# Placa_Alimentaci_n.net
KiCad netlist of a schematic drawn in Altium Designer
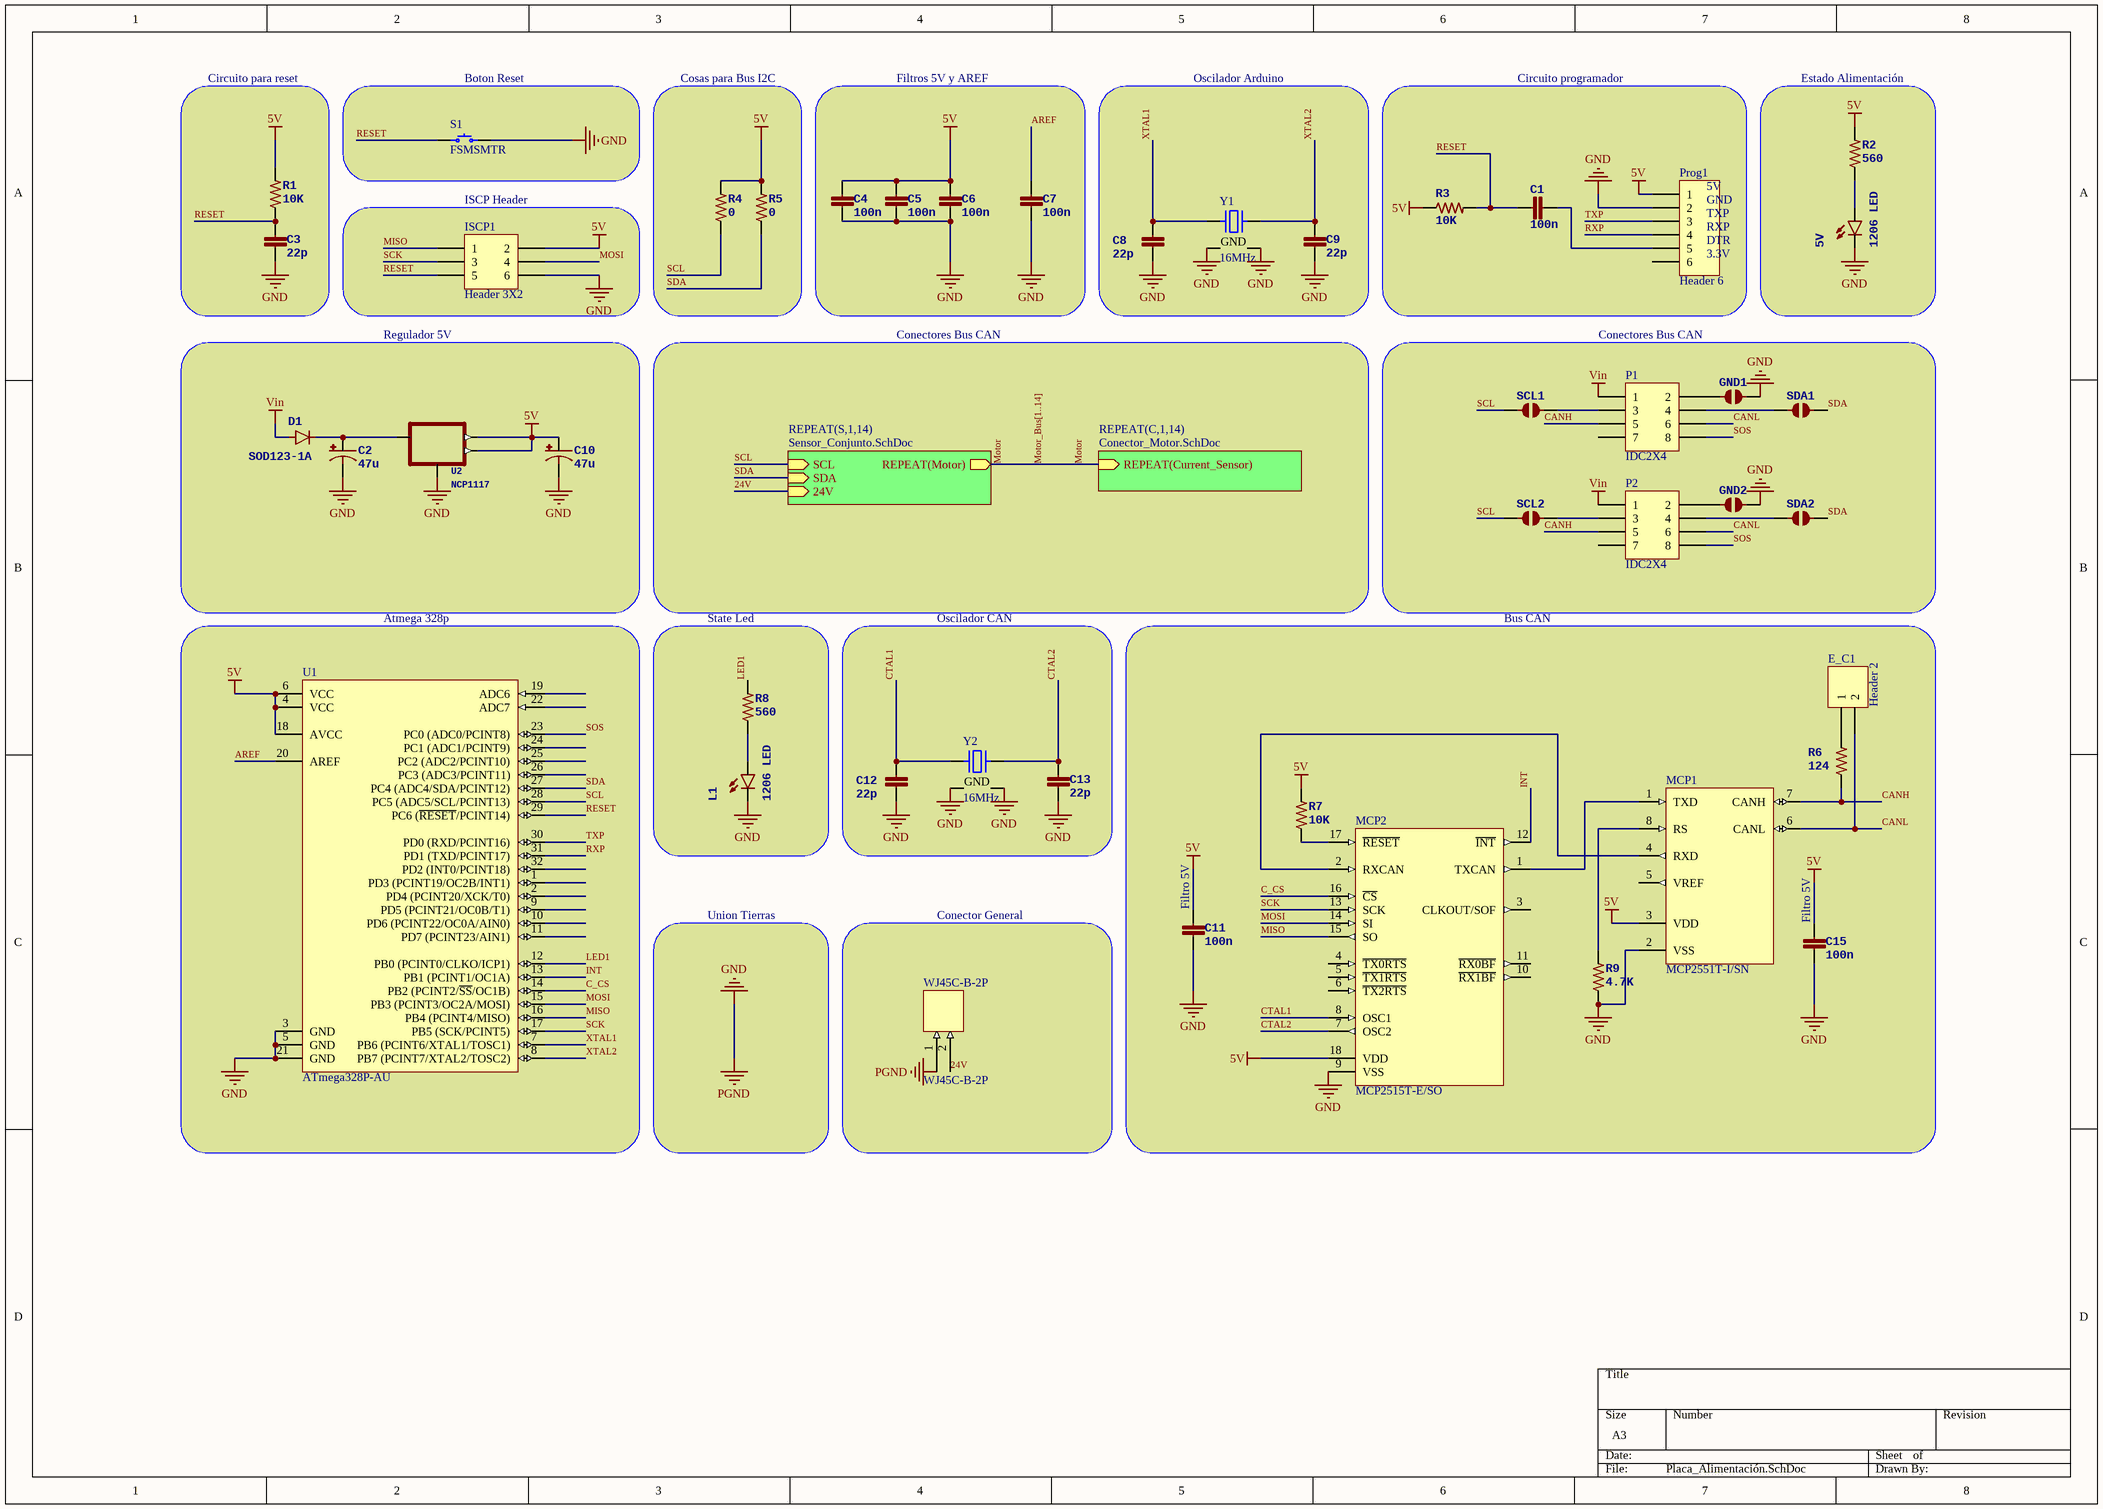
[diagram p0: Placa_Alimentación.SchDoc]

(export (version "E")
  (design (tool "Eeschema 10.0.6"))
  (components
    (comp (ref "5V")
      (value "1206 LED")
      (footprint "SparkFun-LED:LED-1206")
      (libsource (lib "SparkFun-LED") (part "LED1206"))
    )
    (comp (ref "C1")
      (value "100n")
      (footprint "SparkFun-Passives:0805")
      (libsource (lib "") (part "CAP0805_1"))
    )
    (comp (ref "C2")
      (value "47u")
      (footprint "PANASONIC_D")
      (libsource (lib "SparkFun-Capacitors") (part "47UF-50V-20%(ELECT)"))
    )
    (comp (ref "C3")
      (value "22p")
      (footprint "SparkFun-Passives:0805")
      (libsource (lib "SparkFun-Passives") (part "CAP0805"))
    )
    (comp (ref "C4")
      (value "100n")
      (footprint "SparkFun-Passives:0805")
      (libsource (lib "SparkFun-Passives") (part "CAP0805"))
    )
    (comp (ref "C5")
      (value "100n")
      (footprint "SparkFun-Passives:0805")
      (libsource (lib "SparkFun-Passives") (part "CAP0805"))
    )
    (comp (ref "C6")
      (value "100n")
      (footprint "SparkFun-Passives:0805")
      (libsource (lib "SparkFun-Passives") (part "CAP0805"))
    )
    (comp (ref "C7")
      (value "100n")
      (footprint "SparkFun-Passives:0805")
      (libsource (lib "SparkFun-Passives") (part "CAP0805"))
    )
    (comp (ref "C8")
      (value "22p")
      (footprint "SparkFun-Passives:0805")
      (libsource (lib "SparkFun-Passives") (part "CAP0805"))
    )
    (comp (ref "C9")
      (value "22p")
      (footprint "SparkFun-Passives:0805")
      (libsource (lib "SparkFun-Passives") (part "CAP0805"))
    )
    (comp (ref "C10")
      (value "47u")
      (footprint "PANASONIC_D")
      (libsource (lib "SparkFun-Capacitors") (part "47UF-50V-20%(ELECT)"))
    )
    (comp (ref "C11")
      (value "100n")
      (footprint "SparkFun-Passives:0805")
      (libsource (lib "SparkFun-Passives") (part "CAP0805"))
    )
    (comp (ref "C12")
      (value "22p")
      (footprint "SparkFun-Passives:0805")
      (libsource (lib "SparkFun-Passives") (part "CAP0805"))
    )
    (comp (ref "C13")
      (value "22p")
      (footprint "SparkFun-Passives:0805")
      (libsource (lib "SparkFun-Passives") (part "CAP0805"))
    )
    (comp (ref "C15")
      (value "100n")
      (footprint "SparkFun-Passives:0805")
      (libsource (lib "SparkFun-Passives") (part "CAP0805"))
    )
    (comp (ref "D1")
      (value "SOD123-1A")
      (footprint "SOD-123")
      (libsource (lib "SparkFun-DiscreteSemi") (part "DIODESOD123"))
    )
    (comp (ref "E_C1")
      (value "Header 2")
      (footprint "HDR1X2")
      (description "Header, 2-Pin")
      (fields (field (name "PUBLISHER") "Altium Limited"))
      (libsource (lib "Miscellaneous Connectors") (part "Header 2"))
    )
    (comp (ref "GND1")
      (value "JUMPER-PAD-2-NOYES_SILK")
      (footprint "PAD-JUMPER-2-NO_YES_SILK")
      (libsource (lib "SparkFun-Passives") (part "JUMPER-PAD-2-NOYES_SILK"))
    )
    (comp (ref "GND2")
      (value "JUMPER-PAD-2-NOYES_SILK")
      (footprint "PAD-JUMPER-2-NO_YES_SILK")
      (libsource (lib "SparkFun-Passives") (part "JUMPER-PAD-2-NOYES_SILK"))
    )
    (comp (ref "ISCP1")
      (value "Header 3X2")
      (footprint "HDR2X3")
      (description "Header, 3-Pin, Dual row")
      (fields (field (name "PUBLISHER") "Altium Limited"))
      (libsource (lib "Miscellaneous Connectors") (part "Header 3X2"))
    )
    (comp (ref "L1")
      (value "1206 LED")
      (footprint "SparkFun-LED:LED-1206")
      (libsource (lib "SparkFun-LED") (part "LED1206"))
    )
    (comp (ref "MCP1")
      (value "MCP2551T-I/SN")
      (footprint "SOIC-SN8_N")
      (description "High-Speed CAN Transceiver, 8-Pin SOIC, Industrial Temperature, Tape and Reel")
      (fields (field (name "PUBLISHER") "Altium Limited"))
      (libsource (lib "Microchip Interface") (part "MCP2551T-I/SN"))
    )
    (comp (ref "MCP2")
      (value "MCP2515T-E/SO")
      (footprint "SOIC-SO18_N")
      (description "Stand-Alone CAN Controller With SPI Interface, 18-Pin SOIC, Extended Temperature, Tape and Reel")
      (fields (field (name "PUBLISHER") "Altium Limited"))
      (libsource (lib "Microchip Interface") (part "MCP2515T-E/SO"))
    )
    (comp (ref "P1")
      (value "IDC2X4")
      (footprint "IDC2X4")
      (description "Header, 4-Pin, Dual row")
      (fields (field (name "PUBLISHER") "Altium Limited"))
      (libsource (lib "IDC") (part "IDC2X4"))
    )
    (comp (ref "P2")
      (value "IDC2X4")
      (footprint "IDC2X4")
      (description "Header, 4-Pin, Dual row")
      (fields (field (name "PUBLISHER") "Altium Limited"))
      (libsource (lib "IDC") (part "IDC2X4"))
    )
    (comp (ref "Prog1")
      (value "Header 6")
      (footprint "HDR1X6")
      (description "Header, 6-Pin")
      (fields (field (name "PUBLISHER") "Altium Limited"))
      (libsource (lib "Miscellaneous Connectors") (part "Header 6"))
    )
    (comp (ref "R1")
      (value "10K")
      (footprint "SparkFun-Passives:0805")
      (libsource (lib "SparkFun-Passives") (part "RESISTOR0805-RES"))
    )
    (comp (ref "R2")
      (value "560")
      (footprint "SparkFun-Passives:0805")
      (libsource (lib "SparkFun-Passives") (part "RESISTOR0805-RES"))
    )
    (comp (ref "R3")
      (value "10K")
      (footprint "SparkFun-Passives:0805")
      (libsource (lib "SparkFun-Passives") (part "RESISTOR0805-RES"))
    )
    (comp (ref "R4")
      (value "0")
      (footprint "SparkFun-Passives:0805")
      (libsource (lib "SparkFun-Passives") (part "RESISTOR0805-RES"))
    )
    (comp (ref "R5")
      (value "0")
      (footprint "SparkFun-Passives:0805")
      (libsource (lib "SparkFun-Passives") (part "RESISTOR0805-RES"))
    )
    (comp (ref "R6")
      (value "124")
      (footprint "SparkFun-Passives:0805")
      (libsource (lib "SparkFun-Passives") (part "RESISTOR0805-RES"))
    )
    (comp (ref "R7")
      (value "10K")
      (footprint "SparkFun-Passives:0805")
      (libsource (lib "SparkFun-Passives") (part "RESISTOR0805-RES"))
    )
    (comp (ref "R8")
      (value "560")
      (footprint "SparkFun-Passives:0805")
      (libsource (lib "SparkFun-Passives") (part "RESISTOR0805-RES"))
    )
    (comp (ref "R9")
      (value "4.7K")
      (footprint "SparkFun-Passives:0805")
      (libsource (lib "SparkFun-Passives") (part "RESISTOR0805-RES"))
    )
    (comp (ref "S1")
      (value "FSMSMTR")
      (footprint "TE FSMSMTR")
      (description "SWITCH TACTILE SPST-NO 0.05A 24V")
      (fields (field (name "MANUFACTURER") "TE Connectivity Alcoswitch Switches"))
      (libsource (lib "Button - Tactile") (part "SPST-NO 2 PIN"))
    )
    (comp (ref "SCL1")
      (value "JUMPER-PAD-2-NOYES_SILK")
      (footprint "PAD-JUMPER-2-NO_YES_SILK")
      (libsource (lib "SparkFun-Passives") (part "JUMPER-PAD-2-NOYES_SILK"))
    )
    (comp (ref "SCL2")
      (value "JUMPER-PAD-2-NOYES_SILK")
      (footprint "PAD-JUMPER-2-NO_YES_SILK")
      (libsource (lib "SparkFun-Passives") (part "JUMPER-PAD-2-NOYES_SILK"))
    )
    (comp (ref "SDA1")
      (value "JUMPER-PAD-2-NOYES_SILK")
      (footprint "PAD-JUMPER-2-NO_YES_SILK")
      (libsource (lib "SparkFun-Passives") (part "JUMPER-PAD-2-NOYES_SILK"))
    )
    (comp (ref "SDA2")
      (value "JUMPER-PAD-2-NOYES_SILK")
      (footprint "PAD-JUMPER-2-NO_YES_SILK")
      (libsource (lib "SparkFun-Passives") (part "JUMPER-PAD-2-NOYES_SILK"))
    )
    (comp (ref "U1")
      (value "ATmega328P-AU")
      (footprint "32A_N")
      (fields (field (name "PUBLISHER") "Altium Limited"))
      (libsource (lib "Atmel Microcontroller 8-Bit megaAVR") (part "ATmega328P-AU"))
    )
    (comp (ref "U2")
      (value "NCP1117")
      (footprint "SparkFun-IC-Power:SOT223")
      (libsource (lib "SparkFun-IC-Power") (part "V_REG_LM1117SOT223"))
    )
    (comp (ref "WJ45C-B-2P")
      (value "WJ45C-B-2P")
      (footprint "WJ45C-B-2P")
      (libsource (lib "WJ45C") (part "WJ45C-B-2P"))
    )
    (comp (ref "Y1")
      (value "16MHz")
      (footprint "NDK NX3225SA")
      (description "CRYSTAL 16.0000MHZ 8PF SMD")
      (fields (field (name "PART NUMBER") "NX3225SA-16.000MHZ-STD-CSR-1") (field (name "MANUFACTURER") "NDK"))
      (libsource (lib "Oscillator - Crystal") (part "NDK Crystal NX3225SA"))
    )
    (comp (ref "Y2")
      (value "16MHz")
      (footprint "NDK NX3225SA")
      (description "CRYSTAL 16.0000MHZ 8PF SMD")
      (fields (field (name "PART NUMBER") "NX3225SA-16.000MHZ-STD-CSR-1") (field (name "MANUFACTURER") "NDK"))
      (libsource (lib "Oscillator - Crystal") (part "NDK Crystal NX3225SA"))
    )
  )
  (nets
    (net (code "15") (name "/24V") (class "Default") (node (ref "WJ45C-B-2P") (pin "2") (pintype "input")))
    (net (code "16") (name "/AREF") (class "Default")
      (node (ref "C7") (pin "1") (pinfunction "1_1") (pintype "passive"))
      (node (ref "U1") (pin "20") (pinfunction "AREF_20") (pintype "passive"))
    )
    (net (code "17") (name "/CANH") (class "Default")
      (node (ref "MCP1") (pin "7") (pinfunction "CANH_7") (pintype "bidirectional"))
      (node (ref "P1") (pin "5") (pinfunction "5_5") (pintype "passive"))
      (node (ref "P2") (pin "5") (pinfunction "5_5") (pintype "passive"))
      (node (ref "R6") (pin "1") (pinfunction "1_1") (pintype "passive"))
    )
    (net (code "18") (name "/CANL") (class "Default")
      (node (ref "E_C1") (pin "2") (pinfunction "2_2") (pintype "passive"))
      (node (ref "MCP1") (pin "6") (pinfunction "CANL_6") (pintype "bidirectional"))
      (node (ref "P1") (pin "6") (pinfunction "6_6") (pintype "passive"))
      (node (ref "P2") (pin "6") (pinfunction "6_6") (pintype "passive"))
    )
    (net (code "19") (name "/CTAL1") (class "Default")
      (node (ref "C12") (pin "1") (pinfunction "1_1") (pintype "passive"))
      (node (ref "MCP2") (pin "8") (pinfunction "OSC1_8") (pintype "input"))
      (node (ref "Y2") (pin "1") (pinfunction "1_1") (pintype "passive"))
    )
    (net (code "20") (name "/CTAL2") (class "Default")
      (node (ref "C13") (pin "1") (pinfunction "1_1") (pintype "passive"))
      (node (ref "MCP2") (pin "7") (pinfunction "OSC2_7") (pintype "output"))
      (node (ref "Y2") (pin "3") (pinfunction "3_3") (pintype "passive"))
    )
    (net (code "21") (name "/C_CS") (class "Default")
      (node (ref "MCP2") (pin "16") (pinfunction "~{CS}_16") (pintype "input"))
      (node (ref "U1") (pin "14") (pinfunction "PB2_(PCINT2/~{SS}/OC1B)_14") (pintype "bidirectional"))
    )
    (net (code "22") (name "/INT") (class "Default")
      (node (ref "MCP2") (pin "12") (pinfunction "~{INT}_12") (pintype "output"))
      (node (ref "U1") (pin "13") (pinfunction "PB1_(PCINT1/OC1A)_13") (pintype "bidirectional"))
    )
    (net (code "23") (name "/LED1") (class "Default")
      (node (ref "R8") (pin "2") (pinfunction "2_2") (pintype "passive"))
      (node (ref "U1") (pin "12") (pinfunction "PB0_(PCINT0/CLKO/ICP1)_12") (pintype "bidirectional"))
    )
    (net (code "24") (name "/MISO") (class "Default")
      (node (ref "ISCP1") (pin "1") (pinfunction "1_1") (pintype "passive"))
      (node (ref "MCP2") (pin "15") (pinfunction "SO_15") (pintype "output"))
      (node (ref "U1") (pin "16") (pinfunction "PB4_(PCINT4/MISO)_16") (pintype "bidirectional"))
    )
    (net (code "25") (name "/MOSI") (class "Default")
      (node (ref "ISCP1") (pin "4") (pinfunction "4_4") (pintype "passive"))
      (node (ref "MCP2") (pin "14") (pinfunction "SI_14") (pintype "input"))
      (node (ref "U1") (pin "15") (pinfunction "PB3_(PCINT3/OC2A/MOSI)_15") (pintype "bidirectional"))
    )
    (net (code "28") (name "/RESET") (class "Default")
      (node (ref "C1") (pin "1") (pinfunction "1_1") (pintype "passive"))
      (node (ref "C3") (pin "1") (pinfunction "1_1") (pintype "passive"))
      (node (ref "ISCP1") (pin "5") (pinfunction "5_5") (pintype "passive"))
      (node (ref "R1") (pin "1") (pinfunction "1_1") (pintype "passive"))
      (node (ref "R3") (pin "2") (pinfunction "2_2") (pintype "passive"))
      (node (ref "S1") (pin "1") (pinfunction "1_1") (pintype "passive"))
      (node (ref "U1") (pin "29") (pinfunction "PC6_(~{RESET}/PCINT14)_29") (pintype "bidirectional"))
    )
    (net (code "29") (name "/RXP") (class "Default")
      (node (ref "Prog1") (pin "4") (pinfunction "4_4") (pintype "passive"))
      (node (ref "U1") (pin "31") (pinfunction "PD1_(TXD/PCINT17)_31") (pintype "bidirectional"))
    )
    (net (code "30") (name "/SCK") (class "Default")
      (node (ref "ISCP1") (pin "3") (pinfunction "3_3") (pintype "passive"))
      (node (ref "MCP2") (pin "13") (pinfunction "SCK_13") (pintype "input"))
      (node (ref "U1") (pin "17") (pinfunction "PB5_(SCK/PCINT5)_17") (pintype "bidirectional"))
    )
    (net (code "31") (name "/SCL") (class "Default")
      (node (ref "R4") (pin "1") (pinfunction "1_1") (pintype "passive"))
      (node (ref "SCL1") (pin "1") (pinfunction "1_1") (pintype "passive"))
      (node (ref "SCL2") (pin "1") (pinfunction "1_1") (pintype "passive"))
      (node (ref "U1") (pin "28") (pinfunction "PC5_(ADC5/SCL/PCINT13)_28") (pintype "bidirectional"))
    )
    (net (code "32") (name "/SDA") (class "Default")
      (node (ref "R5") (pin "1") (pinfunction "1_1") (pintype "passive"))
      (node (ref "SDA1") (pin "2") (pinfunction "2_2") (pintype "passive"))
      (node (ref "SDA2") (pin "2") (pinfunction "2_2") (pintype "passive"))
      (node (ref "U1") (pin "27") (pinfunction "PC4_(ADC4/SDA/PCINT12)_27") (pintype "bidirectional"))
    )
    (net (code "33") (name "/SOS") (class "Default")
      (node (ref "P1") (pin "8") (pinfunction "8_8") (pintype "passive"))
      (node (ref "P2") (pin "8") (pinfunction "8_8") (pintype "passive"))
      (node (ref "U1") (pin "23") (pinfunction "PC0_(ADC0/PCINT8)_23") (pintype "bidirectional"))
    )
    (net (code "34") (name "/TXP") (class "Default")
      (node (ref "Prog1") (pin "3") (pinfunction "3_3") (pintype "passive"))
      (node (ref "U1") (pin "30") (pinfunction "PD0_(RXD/PCINT16)_30") (pintype "bidirectional"))
    )
    (net (code "35") (name "/XTAL1") (class "Default")
      (node (ref "C8") (pin "1") (pinfunction "1_1") (pintype "passive"))
      (node (ref "U1") (pin "7") (pinfunction "PB6_(PCINT6/XTAL1/TOSC1)_7") (pintype "bidirectional"))
      (node (ref "Y1") (pin "1") (pinfunction "1_1") (pintype "passive"))
    )
    (net (code "36") (name "/XTAL2") (class "Default")
      (node (ref "C9") (pin "1") (pinfunction "1_1") (pintype "passive"))
      (node (ref "U1") (pin "8") (pinfunction "PB7_(PCINT7/XTAL2/TOSC2)_8") (pintype "bidirectional"))
      (node (ref "Y1") (pin "3") (pinfunction "3_3") (pintype "passive"))
    )
    (net (code "37") (name "5V") (class "Default")
      (node (ref "C10") (pin "+") (pinfunction "+_+") (pintype "passive"))
      (node (ref "C11") (pin "1") (pinfunction "1_1") (pintype "passive"))
      (node (ref "C15") (pin "1") (pinfunction "1_1") (pintype "passive"))
      (node (ref "C4") (pin "1") (pinfunction "1_1") (pintype "passive"))
      (node (ref "C5") (pin "1") (pinfunction "1_1") (pintype "passive"))
      (node (ref "C6") (pin "1") (pinfunction "1_1") (pintype "passive"))
      (node (ref "ISCP1") (pin "2") (pinfunction "2_2") (pintype "passive"))
      (node (ref "MCP1") (pin "3") (pinfunction "VDD_3") (pintype "power_in"))
      (node (ref "MCP2") (pin "18") (pinfunction "VDD_18") (pintype "power_in"))
      (node (ref "Prog1") (pin "1") (pinfunction "1_1") (pintype "passive"))
      (node (ref "R1") (pin "2") (pinfunction "2_2") (pintype "passive"))
      (node (ref "R2") (pin "2") (pinfunction "2_2") (pintype "passive"))
      (node (ref "R3") (pin "1") (pinfunction "1_1") (pintype "passive"))
      (node (ref "R4") (pin "2") (pinfunction "2_2") (pintype "passive"))
      (node (ref "R5") (pin "2") (pinfunction "2_2") (pintype "passive"))
      (node (ref "R7") (pin "2") (pinfunction "2_2") (pintype "passive"))
      (node (ref "U1") (pin "18") (pinfunction "AVCC_18") (pintype "power_in"))
      (node (ref "U1") (pin "4") (pinfunction "VCC_4") (pintype "power_in"))
      (node (ref "U1") (pin "6") (pinfunction "VCC_6") (pintype "power_in"))
      (node (ref "U2") (pin "2") (pinfunction "OUT_2") (pintype "output"))
      (node (ref "U2") (pin "4") (pinfunction "OUT@1_4") (pintype "output"))
    )
    (net (code "38") (name "GND") (class "Default")
      (node (ref "5V") (pin "C") (pinfunction "C_C") (pintype "passive"))
      (node (ref "C10") (pin "-") (pinfunction "-_-") (pintype "passive"))
      (node (ref "C11") (pin "2") (pinfunction "2_2") (pintype "passive"))
      (node (ref "C12") (pin "2") (pinfunction "2_2") (pintype "passive"))
      (node (ref "C13") (pin "2") (pinfunction "2_2") (pintype "passive"))
      (node (ref "C15") (pin "2") (pinfunction "2_2") (pintype "passive"))
      (node (ref "C2") (pin "-") (pinfunction "-_-") (pintype "passive"))
      (node (ref "C3") (pin "2") (pinfunction "2_2") (pintype "passive"))
      (node (ref "C4") (pin "2") (pinfunction "2_2") (pintype "passive"))
      (node (ref "C5") (pin "2") (pinfunction "2_2") (pintype "passive"))
      (node (ref "C6") (pin "2") (pinfunction "2_2") (pintype "passive"))
      (node (ref "C7") (pin "2") (pinfunction "2_2") (pintype "passive"))
      (node (ref "C8") (pin "2") (pinfunction "2_2") (pintype "passive"))
      (node (ref "C9") (pin "2") (pinfunction "2_2") (pintype "passive"))
      (node (ref "GND1") (pin "2") (pinfunction "2_2") (pintype "passive"))
      (node (ref "GND2") (pin "2") (pinfunction "2_2") (pintype "passive"))
      (node (ref "ISCP1") (pin "6") (pinfunction "6_6") (pintype "passive"))
      (node (ref "L1") (pin "C") (pinfunction "C_C") (pintype "passive"))
      (node (ref "MCP1") (pin "2") (pinfunction "VSS_2") (pintype "power_in"))
      (node (ref "MCP2") (pin "9") (pinfunction "VSS_9") (pintype "power_in"))
      (node (ref "Prog1") (pin "2") (pinfunction "2_2") (pintype "passive"))
      (node (ref "R9") (pin "1") (pinfunction "1_1") (pintype "passive"))
      (node (ref "S1") (pin "2") (pinfunction "2_2") (pintype "passive"))
      (node (ref "U1") (pin "21") (pinfunction "GND_21") (pintype "power_in"))
      (node (ref "U1") (pin "3") (pinfunction "GND_3") (pintype "power_in"))
      (node (ref "U1") (pin "5") (pinfunction "GND_5") (pintype "power_in"))
      (node (ref "U2") (pin "1") (pinfunction "ADJ_1") (pintype "passive"))
      (node (ref "WJ45C-B-2P") (pin "1") (pintype "input"))
      (node (ref "Y1") (pin "2") (pinfunction "GND_2") (pintype "passive"))
      (node (ref "Y1") (pin "4") (pinfunction "GND_4") (pintype "passive"))
      (node (ref "Y2") (pin "2") (pinfunction "GND_2") (pintype "passive"))
      (node (ref "Y2") (pin "4") (pinfunction "GND_4") (pintype "passive"))
    )
    (net (code "39") (name "Net-(5V-PadA)") (class "Default")
      (node (ref "5V") (pin "A") (pinfunction "A_A") (pintype "passive"))
      (node (ref "R2") (pin "1") (pinfunction "1_1") (pintype "passive"))
    )
    (net (code "40") (name "Net-(C1-Pad2)") (class "Default")
      (node (ref "C1") (pin "2") (pinfunction "2_2") (pintype "passive"))
      (node (ref "Prog1") (pin "5") (pinfunction "5_5") (pintype "passive"))
    )
    (net (code "41") (name "Net-(E_C1-Pad1)") (class "Default")
      (node (ref "E_C1") (pin "1") (pinfunction "1_1") (pintype "passive"))
      (node (ref "R6") (pin "2") (pinfunction "2_2") (pintype "passive"))
    )
    (net (code "42") (name "Net-(GND1-Pad1)") (class "Default")
      (node (ref "GND1") (pin "1") (pinfunction "1_1") (pintype "passive"))
      (node (ref "P1") (pin "2") (pinfunction "2_2") (pintype "passive"))
    )
    (net (code "43") (name "Net-(GND2-Pad1)") (class "Default")
      (node (ref "GND2") (pin "1") (pinfunction "1_1") (pintype "passive"))
      (node (ref "P2") (pin "2") (pinfunction "2_2") (pintype "passive"))
    )
    (net (code "44") (name "Net-(L1-PadA)") (class "Default")
      (node (ref "L1") (pin "A") (pinfunction "A_A") (pintype "passive"))
      (node (ref "R8") (pin "1") (pinfunction "1_1") (pintype "passive"))
    )
    (net (code "45") (name "Net-(MCP1-RS)") (class "Default")
      (node (ref "MCP1") (pin "8") (pinfunction "RS_8") (pintype "input"))
      (node (ref "R9") (pin "2") (pinfunction "2_2") (pintype "passive"))
    )
    (net (code "46") (name "Net-(MCP1-RXD)") (class "Default")
      (node (ref "MCP1") (pin "4") (pinfunction "RXD_4") (pintype "output"))
      (node (ref "MCP2") (pin "2") (pinfunction "RXCAN_2") (pintype "input"))
    )
    (net (code "47") (name "Net-(MCP1-TXD)") (class "Default")
      (node (ref "MCP1") (pin "1") (pinfunction "TXD_1") (pintype "input"))
      (node (ref "MCP2") (pin "1") (pinfunction "TXCAN_1") (pintype "output"))
    )
    (net (code "48") (name "Net-(MCP2-~{RESET})") (class "Default")
      (node (ref "MCP2") (pin "17") (pinfunction "~{RESET}_17") (pintype "input"))
      (node (ref "R7") (pin "1") (pinfunction "1_1") (pintype "passive"))
    )
    (net (code "49") (name "Net-(P1-Pad3)") (class "Default")
      (node (ref "P1") (pin "3") (pinfunction "3_3") (pintype "passive"))
      (node (ref "SCL1") (pin "2") (pinfunction "2_2") (pintype "passive"))
    )
    (net (code "50") (name "Net-(P1-Pad4)") (class "Default")
      (node (ref "P1") (pin "4") (pinfunction "4_4") (pintype "passive"))
      (node (ref "SDA1") (pin "1") (pinfunction "1_1") (pintype "passive"))
    )
    (net (code "51") (name "Net-(P2-Pad3)") (class "Default")
      (node (ref "P2") (pin "3") (pinfunction "3_3") (pintype "passive"))
      (node (ref "SCL2") (pin "2") (pinfunction "2_2") (pintype "passive"))
    )
    (net (code "52") (name "Net-(P2-Pad4)") (class "Default")
      (node (ref "P2") (pin "4") (pinfunction "4_4") (pintype "passive"))
      (node (ref "SDA2") (pin "1") (pinfunction "1_1") (pintype "passive"))
    )
    (net (code "53") (name "Net-(U2-IN)") (class "Default")
      (node (ref "C2") (pin "+") (pinfunction "+_+") (pintype "passive"))
      (node (ref "D1") (pin "C") (pinfunction "C_C") (pintype "passive"))
      (node (ref "U2") (pin "3") (pinfunction "IN_3") (pintype "passive"))
    )
    (net (code "54") (name "Vin") (class "Default")
      (node (ref "D1") (pin "A") (pinfunction "A_A") (pintype "passive"))
      (node (ref "P1") (pin "1") (pinfunction "1_1") (pintype "passive"))
      (node (ref "P2") (pin "1") (pinfunction "1_1") (pintype "passive"))
    )
    (net (code "55") (name "unconnected-(MCP1-VREF-Pad5)") (class "Default")
      (node (ref "MCP1") (pin "5") (pinfunction "VREF_5") (pintype "output"))
    )
    (net (code "56") (name "unconnected-(MCP2-CLKOUT{slash}SOF-Pad3)") (class "Default")
      (node (ref "MCP2") (pin "3") (pinfunction "CLKOUT/SOF_3") (pintype "output"))
    )
    (net (code "57") (name "unconnected-(MCP2-~{RX0BF}-Pad11)") (class "Default")
      (node (ref "MCP2") (pin "11") (pinfunction "~{RX0BF}_11") (pintype "output"))
    )
    (net (code "58") (name "unconnected-(MCP2-~{RX1BF}-Pad10)") (class "Default")
      (node (ref "MCP2") (pin "10") (pinfunction "~{RX1BF}_10") (pintype "output"))
    )
    (net (code "59") (name "unconnected-(MCP2-~{TX0RTS}-Pad4)") (class "Default")
      (node (ref "MCP2") (pin "4") (pinfunction "~{TX0RTS}_4") (pintype "input"))
    )
    (net (code "60") (name "unconnected-(MCP2-~{TX1RTS}-Pad5)") (class "Default")
      (node (ref "MCP2") (pin "5") (pinfunction "~{TX1RTS}_5") (pintype "input"))
    )
    (net (code "61") (name "unconnected-(MCP2-~{TX2RTS}-Pad6)") (class "Default")
      (node (ref "MCP2") (pin "6") (pinfunction "~{TX2RTS}_6") (pintype "input"))
    )
    (net (code "62") (name "unconnected-(P1-Pad7)") (class "Default")
      (node (ref "P1") (pin "7") (pinfunction "7_7") (pintype "passive"))
    )
    (net (code "63") (name "unconnected-(P2-Pad7)") (class "Default")
      (node (ref "P2") (pin "7") (pinfunction "7_7") (pintype "passive"))
    )
    (net (code "64") (name "unconnected-(Prog1-Pad6)") (class "Default")
      (node (ref "Prog1") (pin "6") (pinfunction "6_6") (pintype "passive"))
    )
    (net (code "65") (name "unconnected-(U1-ADC6-Pad19)") (class "Default")
      (node (ref "U1") (pin "19") (pinfunction "ADC6_19") (pintype "input"))
    )
    (net (code "66") (name "unconnected-(U1-ADC7-Pad22)") (class "Default")
      (node (ref "U1") (pin "22") (pinfunction "ADC7_22") (pintype "input"))
    )
    (net (code "67") (name "unconnected-(U1-PC1_(ADC1{slash}PCINT9)-Pad24)") (class "Default")
      (node (ref "U1") (pin "24") (pinfunction "PC1_(ADC1/PCINT9)_24") (pintype "bidirectional"))
    )
    (net (code "68") (name "unconnected-(U1-PC2_(ADC2{slash}PCINT10)-Pad25)") (class "Default")
      (node (ref "U1") (pin "25") (pinfunction "PC2_(ADC2/PCINT10)_25") (pintype "bidirectional"))
    )
    (net (code "69") (name "unconnected-(U1-PC3_(ADC3{slash}PCINT11)-Pad26)") (class "Default")
      (node (ref "U1") (pin "26") (pinfunction "PC3_(ADC3/PCINT11)_26") (pintype "bidirectional"))
    )
    (net (code "70") (name "unconnected-(U1-PD2_(INT0{slash}PCINT18)-Pad32)") (class "Default")
      (node (ref "U1") (pin "32") (pinfunction "PD2_(INT0/PCINT18)_32") (pintype "bidirectional"))
    )
    (net (code "71") (name "unconnected-(U1-PD3_(PCINT19{slash}OC2B{slash}INT1)-Pad1)") (class "Default")
      (node (ref "U1") (pin "1") (pinfunction "PD3_(PCINT19/OC2B/INT1)_1") (pintype "bidirectional"))
    )
    (net (code "72") (name "unconnected-(U1-PD4_(PCINT20{slash}XCK{slash}T0)-Pad2)") (class "Default")
      (node (ref "U1") (pin "2") (pinfunction "PD4_(PCINT20/XCK/T0)_2") (pintype "bidirectional"))
    )
    (net (code "73") (name "unconnected-(U1-PD5_(PCINT21{slash}OC0B{slash}T1)-Pad9)") (class "Default")
      (node (ref "U1") (pin "9") (pinfunction "PD5_(PCINT21/OC0B/T1)_9") (pintype "bidirectional"))
    )
    (net (code "74") (name "unconnected-(U1-PD6_(PCINT22{slash}OC0A{slash}AIN0)-Pad10)") (class "Default")
      (node (ref "U1") (pin "10") (pinfunction "PD6_(PCINT22/OC0A/AIN0)_10") (pintype "bidirectional"))
    )
    (net (code "75") (name "unconnected-(U1-PD7_(PCINT23{slash}AIN1)-Pad11)") (class "Default")
      (node (ref "U1") (pin "11") (pinfunction "PD7_(PCINT23/AIN1)_11") (pintype "bidirectional"))
    )
  )
)
